# CELL_BALANCE.net
KiCad netlist of a schematic drawn in Altium Designer
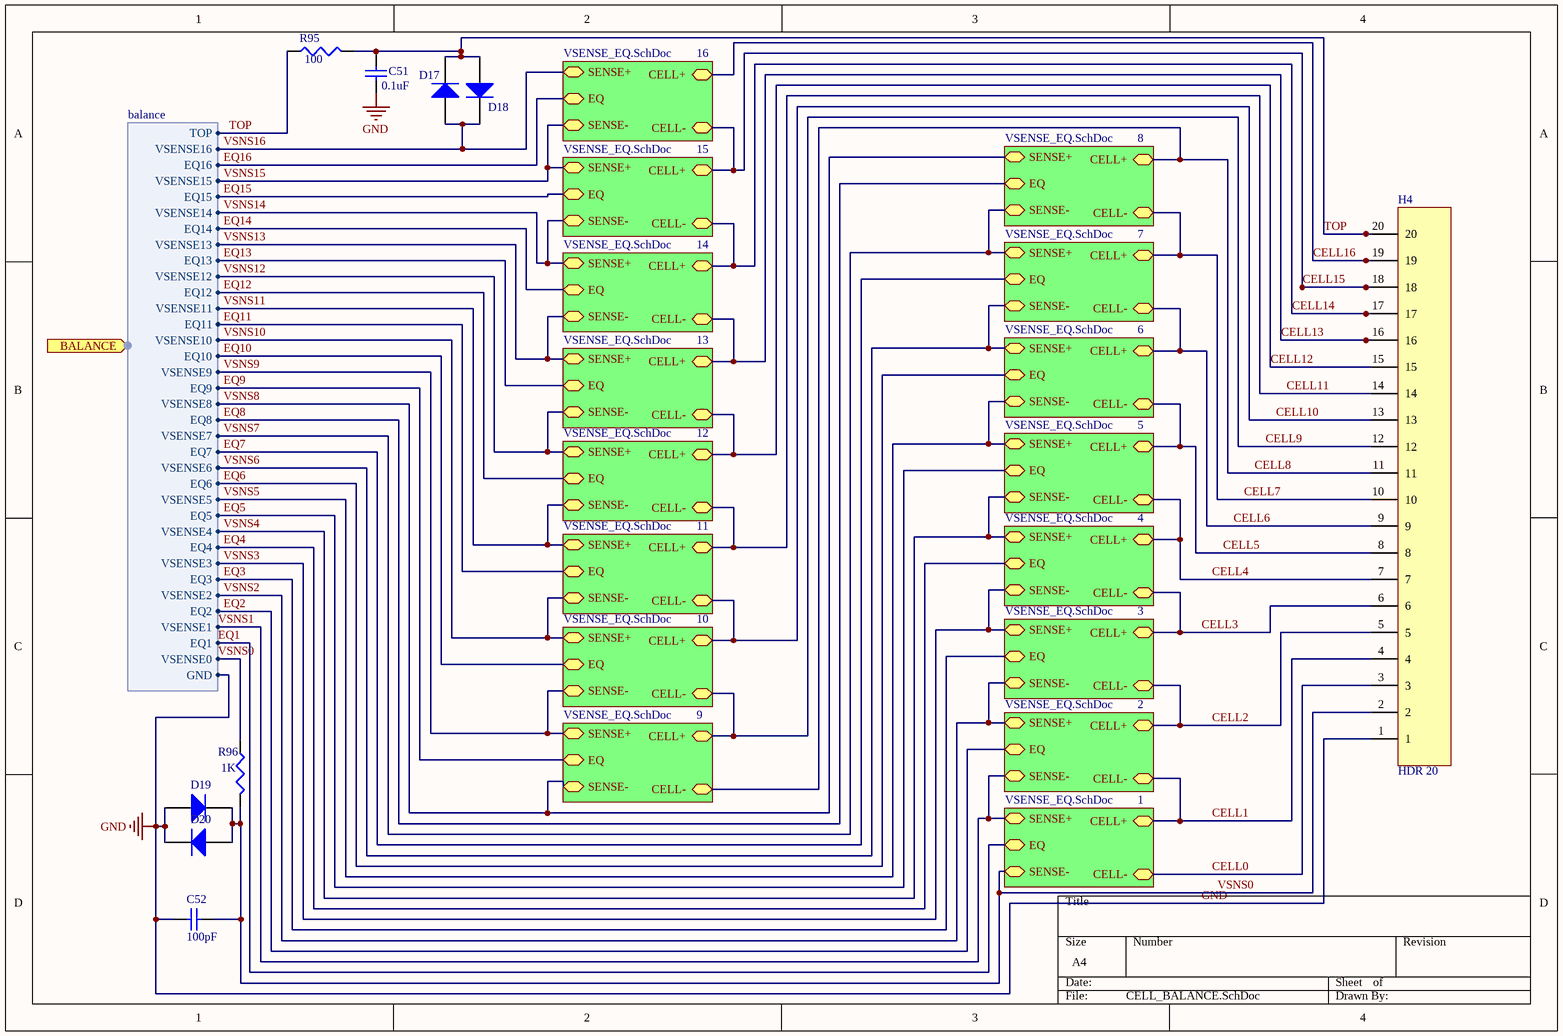
[diagram p0: CELL_BALANCE.SchDoc]

(export (version "E")
  (design (tool "Eeschema 10.0.6"))
  (components
    (comp (ref "C51")
      (value "0.1uF")
      (footprint "1210 cap")
      (description "Capacitor (Semiconductor SIM Model)")
      (fields
        (field (name "MANUFACTURER") "Murata")
        (field (name "MANUFACTURER PART NUMBER") "GRM32NR72A104KA01L")
        (field (name "PUBLISHER") "Altium Limited")
      )
      (libsource (lib "Miscellaneous Devices") (part "Cap Semi"))
    )
    (comp (ref "C52")
      (value "100pF")
      (footprint "0603 CAP")
      (description "Capacitor (Semiconductor SIM Model)")
      (fields
        (field (name "MANUFACTURER") "TDK")
        (field (name "MANUFACTURER PART NUMBER") "C1608X7R1C105K080AC")
        (field (name "PUBLISHER") "Altium Limited")
      )
      (libsource (lib "Miscellaneous Devices") (part "Cap Semi"))
    )
    (comp (ref "D17")
      (value "~")
      (footprint "DIODE BtoB")
      (description "Default Diode")
      (fields
        (field (name "MANUFACTURER") "Diodes")
        (field (name "MANUFACTURER PART NUMBER") "1N4148W-7-F")
        (field (name "PUBLISHER") "Altium Limited")
      )
      (libsource (lib "Miscellaneous Devices") (part "Diode"))
    )
    (comp (ref "D18")
      (value "~")
      (footprint "DIODE BtoB")
      (description "Default Diode")
      (fields
        (field (name "MANUFACTURER") "Diodes")
        (field (name "MANUFACTURER PART NUMBER") "1N4148W-7-F")
        (field (name "PUBLISHER") "Altium Limited")
      )
      (libsource (lib "Miscellaneous Devices") (part "Diode"))
    )
    (comp (ref "D19")
      (value "~")
      (footprint "DIODE BtoB")
      (description "Default Diode")
      (fields
        (field (name "MANUFACTURER") "Diodes")
        (field (name "MANUFACTURER PART NUMBER") "1N4148W-7-F")
        (field (name "PUBLISHER") "Altium Limited")
      )
      (libsource (lib "Miscellaneous Devices") (part "Diode"))
    )
    (comp (ref "D20")
      (value "~")
      (footprint "DIODE BtoB")
      (description "Default Diode")
      (fields
        (field (name "MANUFACTURER") "Diodes")
        (field (name "MANUFACTURER PART NUMBER") "1N4148W-7-F")
        (field (name "PUBLISHER") "Altium Limited")
      )
      (libsource (lib "Miscellaneous Devices") (part "Diode"))
    )
    (comp (ref "H4") (value "HDR 20") (footprint "CELL HDR") (libsource (lib "parts") (part "HDR 20")))
    (comp (ref "R95")
      (value "100")
      (footprint "1206 RES")
      (description "Resistor")
      (fields
        (field (name "MANUFACTURER") "Vishay Dale")
        (field (name "MANUFACTURER PART NUMBER") "CRCW1206100RFKEA")
        (field (name "PUBLISHER") "Altium Limited")
      )
      (libsource (lib "Miscellaneous Devices") (part "Res3"))
    )
    (comp (ref "R96")
      (value "1K")
      (footprint "0603 RES")
      (description "Resistor")
      (fields
        (field (name "MANUFACTURER") "Vishay Dale")
        (field (name "MANUFACTURER PART NUMBER") "CRCW06031K00FKEA")
        (field (name "PUBLISHER") "Altium Limited")
      )
      (libsource (lib "Miscellaneous Devices") (part "Res3"))
    )
  )
  (nets
    (net (code "2") (name "/CELL0") (class "Default")
      (node (ref "H4") (pin "3") (pinfunction "3_3") (pintype "passive"))
    )
    (net (code "3") (name "/CELL1") (class "Default")
      (node (ref "H4") (pin "4") (pinfunction "4_4") (pintype "passive"))
    )
    (net (code "4") (name "/CELL2") (class "Default")
      (node (ref "H4") (pin "5") (pinfunction "5_5") (pintype "passive"))
    )
    (net (code "5") (name "/CELL3") (class "Default")
      (node (ref "H4") (pin "6") (pinfunction "6_6") (pintype "passive"))
    )
    (net (code "6") (name "/CELL4") (class "Default")
      (node (ref "H4") (pin "7") (pinfunction "7_7") (pintype "passive"))
    )
    (net (code "7") (name "/CELL5") (class "Default")
      (node (ref "H4") (pin "8") (pinfunction "8_8") (pintype "passive"))
    )
    (net (code "8") (name "/CELL6") (class "Default")
      (node (ref "H4") (pin "9") (pinfunction "9_9") (pintype "passive"))
    )
    (net (code "9") (name "/CELL7") (class "Default")
      (node (ref "H4") (pin "10") (pinfunction "10_10") (pintype "passive"))
    )
    (net (code "10") (name "/CELL8") (class "Default")
      (node (ref "H4") (pin "11") (pinfunction "11_11") (pintype "passive"))
    )
    (net (code "11") (name "/CELL9") (class "Default")
      (node (ref "H4") (pin "12") (pinfunction "12_12") (pintype "passive"))
    )
    (net (code "12") (name "/CELL10") (class "Default")
      (node (ref "H4") (pin "13") (pinfunction "13_13") (pintype "passive"))
    )
    (net (code "13") (name "/CELL11") (class "Default")
      (node (ref "H4") (pin "14") (pinfunction "14_14") (pintype "passive"))
    )
    (net (code "14") (name "/CELL12") (class "Default")
      (node (ref "H4") (pin "15") (pinfunction "15_15") (pintype "passive"))
    )
    (net (code "15") (name "/CELL13") (class "Default")
      (node (ref "H4") (pin "16") (pinfunction "16_16") (pintype "passive"))
    )
    (net (code "16") (name "/CELL14") (class "Default")
      (node (ref "H4") (pin "17") (pinfunction "17_17") (pintype "passive"))
    )
    (net (code "17") (name "/CELL15") (class "Default")
      (node (ref "H4") (pin "18") (pinfunction "18_18") (pintype "passive"))
    )
    (net (code "18") (name "/CELL16") (class "Default")
      (node (ref "H4") (pin "19") (pinfunction "19_19") (pintype "passive"))
    )
    (net (code "35") (name "/TOP") (class "Default")
      (node (ref "C51") (pin "2") (pinfunction "2_2") (pintype "passive"))
      (node (ref "D17") (pin "2") (pinfunction "K_2") (pintype "passive"))
      (node (ref "D18") (pin "1") (pinfunction "A_1") (pintype "passive"))
      (node (ref "H4") (pin "20") (pinfunction "20_20") (pintype "passive"))
      (node (ref "R95") (pin "1") (pinfunction "1_1") (pintype "passive"))
      (node (ref "R95") (pin "2") (pinfunction "2_2") (pintype "passive"))
    )
    (net (code "36") (name "/VSNS0") (class "Default")
      (node (ref "C52") (pin "2") (pinfunction "2_2") (pintype "passive"))
      (node (ref "D19") (pin "2") (pinfunction "K_2") (pintype "passive"))
      (node (ref "D20") (pin "1") (pinfunction "A_1") (pintype "passive"))
      (node (ref "H4") (pin "2") (pinfunction "2_2") (pintype "passive"))
      (node (ref "R96") (pin "1") (pinfunction "1_1") (pintype "passive"))
      (node (ref "R96") (pin "2") (pinfunction "2_2") (pintype "passive"))
    )
    (net (code "52") (name "/VSNS16") (class "Default")
      (node (ref "D17") (pin "1") (pinfunction "A_1") (pintype "passive"))
      (node (ref "D18") (pin "2") (pinfunction "K_2") (pintype "passive"))
    )
    (net (code "54") (name "GND") (class "Default")
      (node (ref "C51") (pin "1") (pinfunction "1_1") (pintype "passive"))
      (node (ref "C52") (pin "1") (pinfunction "1_1") (pintype "passive"))
      (node (ref "D19") (pin "1") (pinfunction "A_1") (pintype "passive"))
      (node (ref "D20") (pin "2") (pinfunction "K_2") (pintype "passive"))
      (node (ref "H4") (pin "1") (pinfunction "1_1") (pintype "passive"))
    )
  )
)
